# main.net
KiCad netlist of a schematic drawn in EAGLE
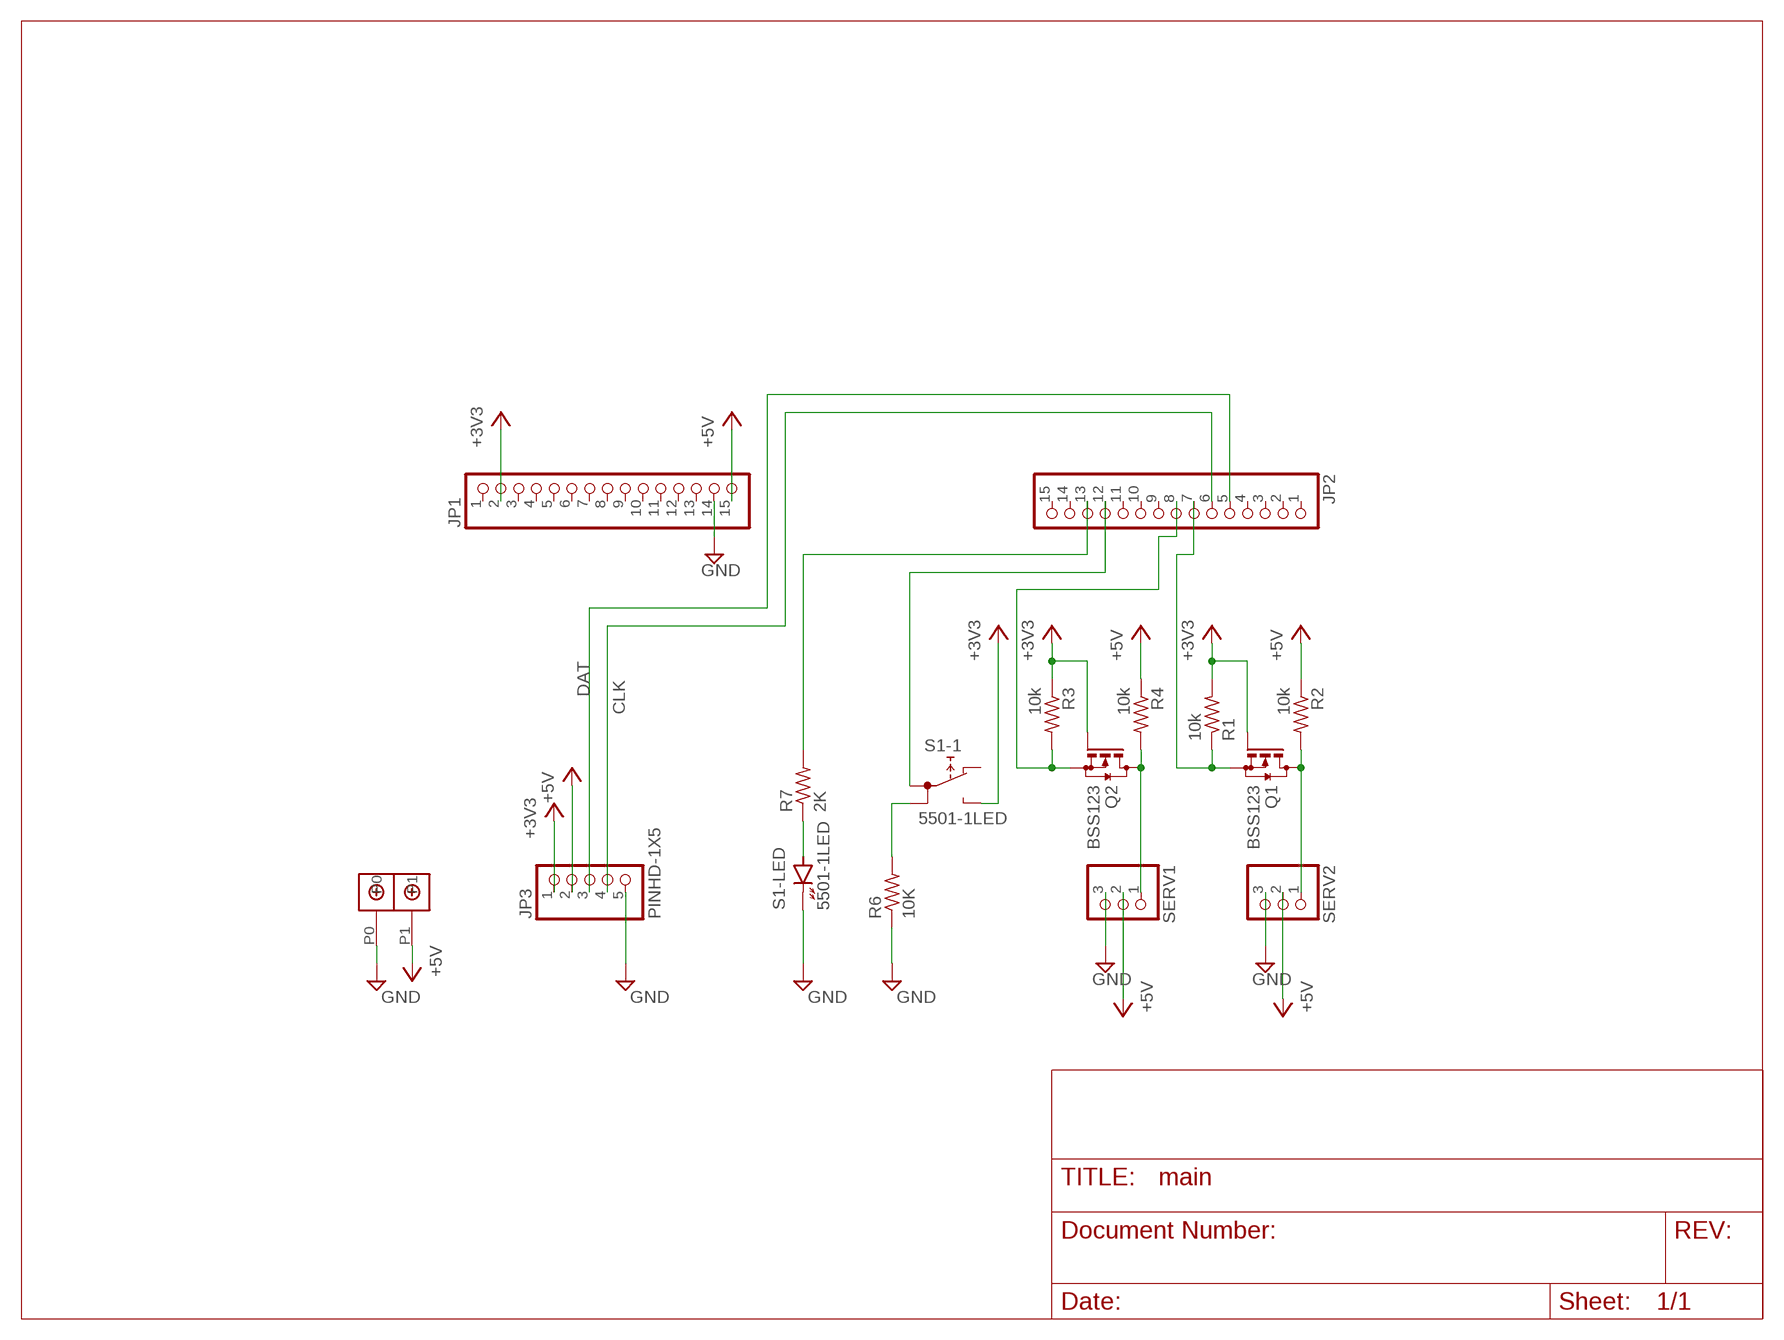
[diagram p0: schematic, sheet 1]

(export (version "E")
  (design (tool "Eeschema 10.0.6"))
  (components
    (comp (ref "JP1")
      (value "PINHD-1X15")
      (footprint "eagle-import:1X15")
      (libsource (lib "eagle-import") (part "PINHD-1X15"))
    )
    (comp (ref "JP2")
      (value "PINHD-1X15")
      (footprint "eagle-import:1X15")
      (libsource (lib "eagle-import") (part "PINHD-1X15"))
    )
    (comp (ref "JP3")
      (value "PINHD-1X5")
      (footprint "eagle-import:1X05")
      (libsource (lib "eagle-import") (part "PINHD-1X5"))
    )
    (comp (ref "Q1")
      (value "BSS123")
      (footprint "eagle-import:SOT23")
      (libsource (lib "eagle-import") (part "BSS123"))
    )
    (comp (ref "Q2")
      (value "BSS123")
      (footprint "eagle-import:SOT23")
      (libsource (lib "eagle-import") (part "BSS123"))
    )
    (comp (ref "R1")
      (value "10k")
      (footprint "eagle-import:M0805")
      (libsource (lib "eagle-import") (part "R-US_M0805"))
    )
    (comp (ref "R2")
      (value "10k")
      (footprint "eagle-import:M0805")
      (libsource (lib "eagle-import") (part "R-US_M0805"))
    )
    (comp (ref "R3")
      (value "10k")
      (footprint "eagle-import:M0805")
      (libsource (lib "eagle-import") (part "R-US_M0805"))
    )
    (comp (ref "R4")
      (value "10k")
      (footprint "eagle-import:M0805")
      (libsource (lib "eagle-import") (part "R-US_M0805"))
    )
    (comp (ref "R6")
      (value "10K")
      (footprint "eagle-import:M0805")
      (libsource (lib "eagle-import") (part "R-US_M0805"))
    )
    (comp (ref "R7")
      (value "2K")
      (footprint "eagle-import:M0805")
      (libsource (lib "eagle-import") (part "R-US_M0805"))
    )
    (comp (ref "S1")
      (value "5501-1LED")
      (footprint "eagle-import:5501-1LED")
      (libsource (lib "eagle-import") (part "55?-1LED01"))
    )
    (comp (ref "SERV1")
      (value "PINHD-1X3")
      (footprint "eagle-import:1X03")
      (libsource (lib "eagle-import") (part "PINHD-1X3"))
    )
    (comp (ref "SERV2")
      (value "PINHD-1X3")
      (footprint "eagle-import:1X03")
      (libsource (lib "eagle-import") (part "PINHD-1X3"))
    )
    (comp (ref "U$1")
      (value "DBCONN-1X2")
      (footprint "eagle-import:DBCONN-1X2")
      (libsource (lib "eagle-import") (part "DBCONN-1X2"))
    )
  )
  (nets
    (net (code "1") (name "+3V3") (class "Default")
      (node (ref "JP1") (pin "2") (pinfunction "2_2") (pintype "passive"))
      (node (ref "JP3") (pin "1") (pinfunction "1_1") (pintype "passive"))
      (node (ref "Q1") (pin "1") (pinfunction "G_1") (pintype "passive"))
      (node (ref "Q2") (pin "1") (pinfunction "G_1") (pintype "passive"))
      (node (ref "R1") (pin "2") (pinfunction "2_2") (pintype "passive"))
      (node (ref "R3") (pin "1") (pinfunction "1_1") (pintype "passive"))
      (node (ref "S1") (pin "NO") (pinfunction "NO_NO") (pintype "passive"))
    )
    (net (code "2") (name "+5V") (class "Default")
      (node (ref "JP1") (pin "15") (pinfunction "15_15") (pintype "passive"))
      (node (ref "JP3") (pin "2") (pinfunction "2_2") (pintype "passive"))
      (node (ref "R2") (pin "1") (pinfunction "1_1") (pintype "passive"))
      (node (ref "R4") (pin "1") (pinfunction "1_1") (pintype "passive"))
      (node (ref "SERV1") (pin "2") (pinfunction "2_2") (pintype "passive"))
      (node (ref "SERV2") (pin "2") (pinfunction "2_2") (pintype "passive"))
      (node (ref "U$1") (pin "P1") (pinfunction "P1_P1") (pintype "bidirectional"))
    )
    (net (code "3") (name "GND") (class "Default")
      (node (ref "JP1") (pin "14") (pinfunction "14_14") (pintype "passive"))
      (node (ref "JP3") (pin "5") (pinfunction "5_5") (pintype "passive"))
      (node (ref "R6") (pin "1") (pinfunction "1_1") (pintype "passive"))
      (node (ref "S1") (pin "-") (pinfunction "K_-") (pintype "passive"))
      (node (ref "SERV1") (pin "3") (pinfunction "3_3") (pintype "passive"))
      (node (ref "SERV2") (pin "3") (pinfunction "3_3") (pintype "passive"))
      (node (ref "U$1") (pin "P0") (pinfunction "P0_P0") (pintype "bidirectional"))
    )
    (net (code "4") (name "Net-(JP2-Pad5)") (class "Default")
      (node (ref "JP2") (pin "5") (pinfunction "5_5") (pintype "passive"))
      (node (ref "JP3") (pin "3") (pinfunction "3_3") (pintype "passive"))
    )
    (net (code "5") (name "Net-(JP2-Pad6)") (class "Default")
      (node (ref "JP2") (pin "6") (pinfunction "6_6") (pintype "passive"))
      (node (ref "JP3") (pin "4") (pinfunction "4_4") (pintype "passive"))
    )
    (net (code "6") (name "Net-(JP2-Pad12)") (class "Default")
      (node (ref "JP2") (pin "12") (pinfunction "12_12") (pintype "passive"))
      (node (ref "S1") (pin "1A") (pinfunction "1A_1A") (pintype "passive"))
    )
    (net (code "7") (name "Net-(JP2-Pad13)") (class "Default")
      (node (ref "JP2") (pin "13") (pinfunction "13_13") (pintype "passive"))
      (node (ref "R7") (pin "2") (pinfunction "2_2") (pintype "passive"))
    )
    (net (code "8") (name "Net-(Q1-D)") (class "Default")
      (node (ref "Q1") (pin "3") (pinfunction "D_3") (pintype "passive"))
      (node (ref "R2") (pin "2") (pinfunction "2_2") (pintype "passive"))
      (node (ref "SERV2") (pin "1") (pinfunction "1_1") (pintype "passive"))
    )
    (net (code "9") (name "Net-(Q1-S)") (class "Default")
      (node (ref "JP2") (pin "7") (pinfunction "7_7") (pintype "passive"))
      (node (ref "Q1") (pin "2") (pinfunction "S_2") (pintype "passive"))
      (node (ref "R1") (pin "1") (pinfunction "1_1") (pintype "passive"))
    )
    (net (code "10") (name "Net-(Q2-D)") (class "Default")
      (node (ref "Q2") (pin "3") (pinfunction "D_3") (pintype "passive"))
      (node (ref "R4") (pin "2") (pinfunction "2_2") (pintype "passive"))
      (node (ref "SERV1") (pin "1") (pinfunction "1_1") (pintype "passive"))
    )
    (net (code "11") (name "Net-(Q2-S)") (class "Default")
      (node (ref "JP2") (pin "8") (pinfunction "8_8") (pintype "passive"))
      (node (ref "Q2") (pin "2") (pinfunction "S_2") (pintype "passive"))
      (node (ref "R3") (pin "2") (pinfunction "2_2") (pintype "passive"))
    )
    (net (code "12") (name "Net-(R6-Pad2)") (class "Default")
      (node (ref "R6") (pin "2") (pinfunction "2_2") (pintype "passive"))
      (node (ref "S1") (pin "1B") (pinfunction "1B_1B") (pintype "passive"))
    )
    (net (code "13") (name "Net-(S1B-A)") (class "Default")
      (node (ref "R7") (pin "1") (pinfunction "1_1") (pintype "passive"))
      (node (ref "S1") (pin "+") (pinfunction "A_+") (pintype "passive"))
    )
    (net (code "14") (name "unconnected-(JP1-Pad1)") (class "Default")
      (node (ref "JP1") (pin "1") (pinfunction "1_1") (pintype "passive"))
    )
    (net (code "15") (name "unconnected-(JP1-Pad3)") (class "Default")
      (node (ref "JP1") (pin "3") (pinfunction "3_3") (pintype "passive"))
    )
    (net (code "16") (name "unconnected-(JP1-Pad4)") (class "Default")
      (node (ref "JP1") (pin "4") (pinfunction "4_4") (pintype "passive"))
    )
    (net (code "17") (name "unconnected-(JP1-Pad5)") (class "Default")
      (node (ref "JP1") (pin "5") (pinfunction "5_5") (pintype "passive"))
    )
    (net (code "18") (name "unconnected-(JP1-Pad6)") (class "Default")
      (node (ref "JP1") (pin "6") (pinfunction "6_6") (pintype "passive"))
    )
    (net (code "19") (name "unconnected-(JP1-Pad7)") (class "Default")
      (node (ref "JP1") (pin "7") (pinfunction "7_7") (pintype "passive"))
    )
    (net (code "20") (name "unconnected-(JP1-Pad8)") (class "Default")
      (node (ref "JP1") (pin "8") (pinfunction "8_8") (pintype "passive"))
    )
    (net (code "21") (name "unconnected-(JP1-Pad9)") (class "Default")
      (node (ref "JP1") (pin "9") (pinfunction "9_9") (pintype "passive"))
    )
    (net (code "22") (name "unconnected-(JP1-Pad10)") (class "Default")
      (node (ref "JP1") (pin "10") (pinfunction "10_10") (pintype "passive"))
    )
    (net (code "23") (name "unconnected-(JP1-Pad11)") (class "Default")
      (node (ref "JP1") (pin "11") (pinfunction "11_11") (pintype "passive"))
    )
    (net (code "24") (name "unconnected-(JP1-Pad12)") (class "Default")
      (node (ref "JP1") (pin "12") (pinfunction "12_12") (pintype "passive"))
    )
    (net (code "25") (name "unconnected-(JP1-Pad13)") (class "Default")
      (node (ref "JP1") (pin "13") (pinfunction "13_13") (pintype "passive"))
    )
    (net (code "26") (name "unconnected-(JP2-Pad1)") (class "Default")
      (node (ref "JP2") (pin "1") (pinfunction "1_1") (pintype "passive"))
    )
    (net (code "27") (name "unconnected-(JP2-Pad2)") (class "Default")
      (node (ref "JP2") (pin "2") (pinfunction "2_2") (pintype "passive"))
    )
    (net (code "28") (name "unconnected-(JP2-Pad3)") (class "Default")
      (node (ref "JP2") (pin "3") (pinfunction "3_3") (pintype "passive"))
    )
    (net (code "29") (name "unconnected-(JP2-Pad4)") (class "Default")
      (node (ref "JP2") (pin "4") (pinfunction "4_4") (pintype "passive"))
    )
    (net (code "30") (name "unconnected-(JP2-Pad9)") (class "Default")
      (node (ref "JP2") (pin "9") (pinfunction "9_9") (pintype "passive"))
    )
    (net (code "31") (name "unconnected-(JP2-Pad10)") (class "Default")
      (node (ref "JP2") (pin "10") (pinfunction "10_10") (pintype "passive"))
    )
    (net (code "32") (name "unconnected-(JP2-Pad11)") (class "Default")
      (node (ref "JP2") (pin "11") (pinfunction "11_11") (pintype "passive"))
    )
    (net (code "33") (name "unconnected-(JP2-Pad14)") (class "Default")
      (node (ref "JP2") (pin "14") (pinfunction "14_14") (pintype "passive"))
    )
    (net (code "34") (name "unconnected-(JP2-Pad15)") (class "Default")
      (node (ref "JP2") (pin "15") (pinfunction "15_15") (pintype "passive"))
    )
    (net (code "35") (name "unconnected-(S1-PadNC)") (class "Default")
      (node (ref "S1") (pin "NC") (pinfunction "NC_NC") (pintype "passive"))
    )
  )
)
